# FSPDL_50_5-51Hz.net
KiCad netlist of a schematic drawn in EasyEDA
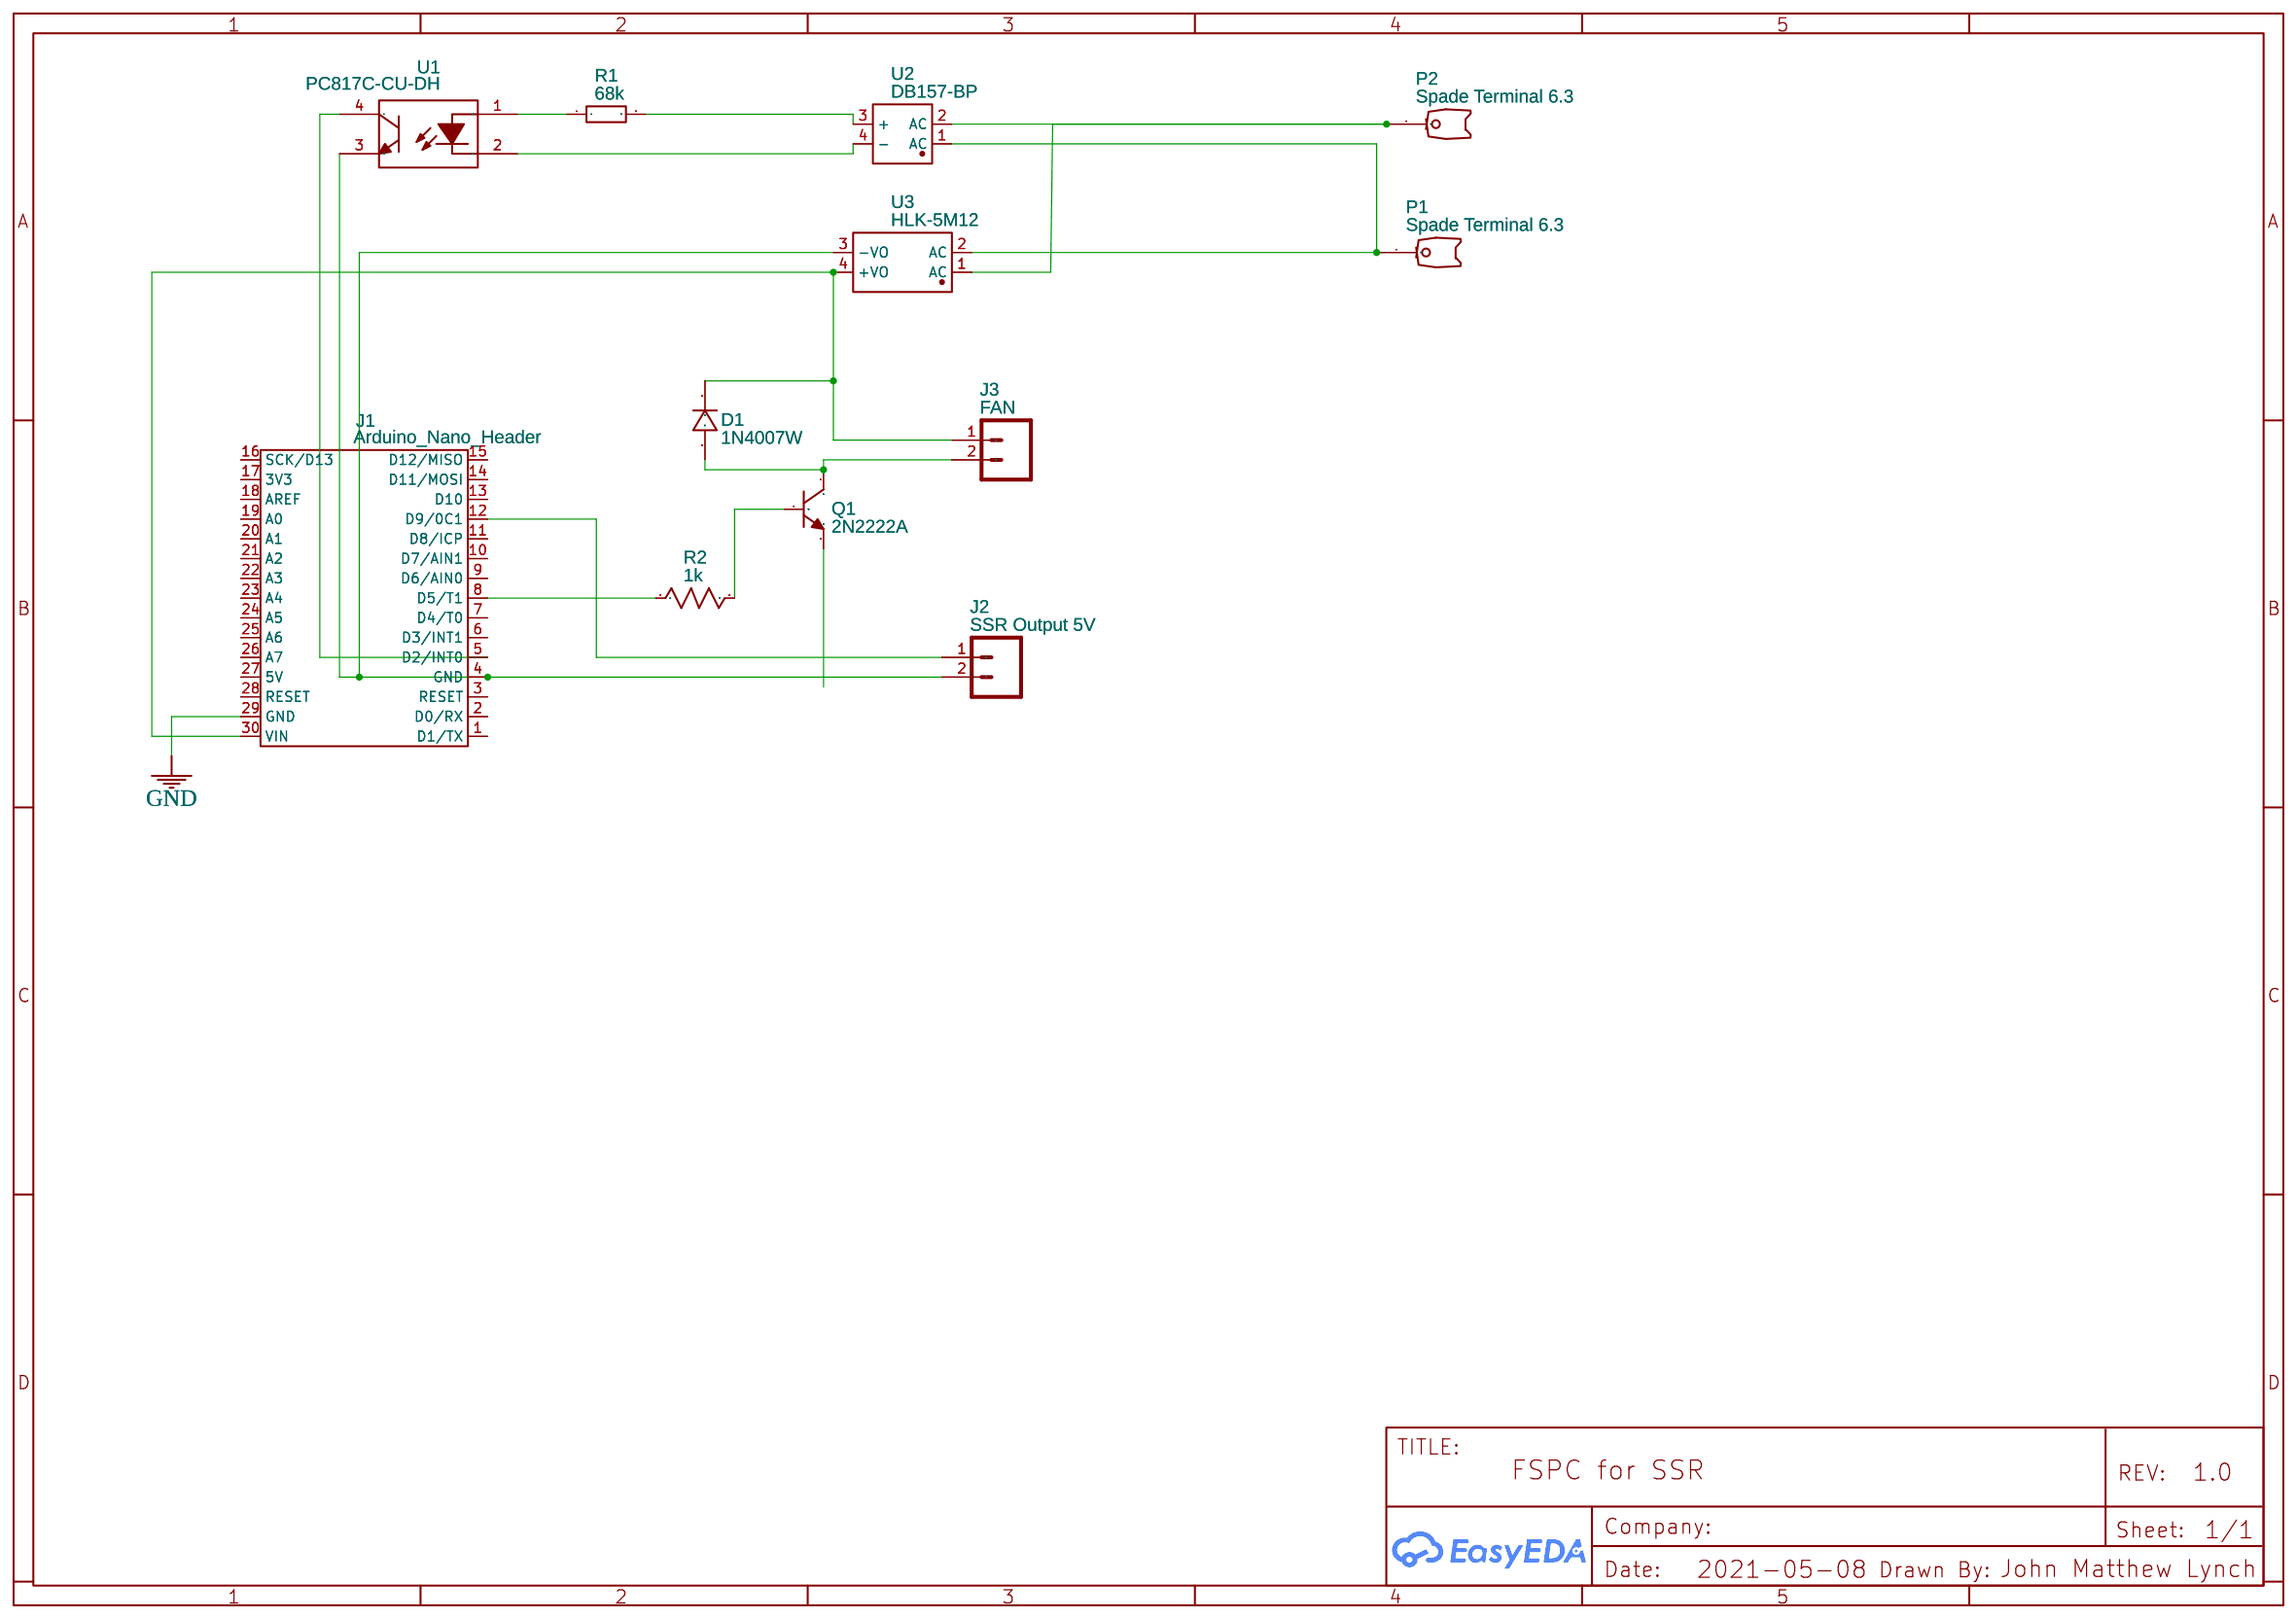
[diagram p0: schematic sheet]

(export (version "E")
  (design (tool "Eeschema 10.0.6"))
  (components
    (comp (ref "D1")
      (value "1N4007W")
      (fields (field (name "BOM_Supplier Part") "C328592"))
      (libsource (lib "") (part "1N4007W"))
    )
    (comp (ref "J1") (value "Arduino_Nano_Header") (libsource (lib "") (part "Arduino_Nano_Header")))
    (comp (ref "J2") (value "SSR Output 5V") (libsource (lib "") (part "CONN_02JST-PTH-2")))
    (comp (ref "J3") (value "FAN") (libsource (lib "") (part "CONN_02JST-PTH-2")))
    (comp (ref "P1")
      (value "Spade Terminal 6.3")
      (fields (field (name "BOM_Manufacturer Part") "1287") (field (name "BOM_Supplier Part") "C238078"))
      (libsource (lib "") (part "Spade Terminal 6.3"))
    )
    (comp (ref "P2")
      (value "Spade Terminal 6.3")
      (fields (field (name "BOM_Manufacturer Part") "1287") (field (name "BOM_Supplier Part") "C238078"))
      (libsource (lib "") (part "Spade Terminal 6.3"))
    )
    (comp (ref "Q1")
      (value "2N2222A")
      (fields (field (name "Manufacturer") "BLUE ROCKET(蓝箭)"))
      (libsource (lib "") (part "2N2222A"))
    )
    (comp (ref "R1")
      (value "68k")
      (fields (field (name "BOM_Supplier Part") "C119513"))
      (libsource (lib "") (part "1W 68K"))
    )
    (comp (ref "R2") (value "1k") (libsource (lib "") (part "R_0603_US")))
    (comp (ref "U1")
      (value "PC817C-CU-DH")
      (fields (field (name "BOM_Supplier Part") "C427589"))
      (libsource (lib "") (part "PC817C-CU-DH"))
    )
    (comp (ref "U2")
      (value "DB157-BP")
      (fields (field (name "BOM_Supplier Part") "C2975492"))
      (libsource (lib "") (part "DB157-BP"))
    )
    (comp (ref "U3")
      (value "HLK-5M12")
      (fields (field (name "BOM_Supplier Part") "C209908"))
      (libsource (lib "") (part "HLK-5M12"))
    )
  )
  (nets
    (net (code "1") (name "GND") (class "Default")
      (node (ref "J1") (pin "29") (pinfunction "GND_29") (pintype "unspecified"))
    )
    (net (code "2") (name "Net-(J1-D2{slash}INT0)") (class "Default")
      (node (ref "J1") (pin "5") (pinfunction "D2/INT0_5") (pintype "unspecified"))
      (node (ref "U1") (pin "4") (pinfunction "4_4") (pintype "unspecified"))
    )
    (net (code "3") (name "Net-(J1-D5{slash}T1)") (class "Default")
      (node (ref "J1") (pin "8") (pinfunction "D5/T1_8") (pintype "unspecified"))
      (node (ref "R2") (pin "1") (pinfunction "1_1") (pintype "unspecified"))
    )
    (net (code "4") (name "Net-(J1-D9{slash}0C1)") (class "Default")
      (node (ref "J1") (pin "12") (pinfunction "D9/0C1_12") (pintype "unspecified"))
      (node (ref "J2") (pin "1") (pinfunction "1_1") (pintype "unspecified"))
    )
    (net (code "5") (name "Net-(J1-VIN)") (class "Default")
      (node (ref "D1") (pin "1") (pinfunction "1_1") (pintype "unspecified"))
      (node (ref "J1") (pin "30") (pinfunction "VIN_30") (pintype "unspecified"))
      (node (ref "J3") (pin "1") (pinfunction "1_1") (pintype "unspecified"))
      (node (ref "U3") (pin "4") (pinfunction "+VO_4") (pintype "unspecified"))
    )
    (net (code "6") (name "Net-(P1-Pad1)") (class "Default")
      (node (ref "P1") (pin "1") (pinfunction "1_1") (pintype "unspecified"))
      (node (ref "U2") (pin "1") (pinfunction "AC_1") (pintype "unspecified"))
      (node (ref "U3") (pin "2") (pinfunction "AC_2") (pintype "unspecified"))
    )
    (net (code "7") (name "Net-(P2-Pad1)") (class "Default")
      (node (ref "P2") (pin "1") (pinfunction "1_1") (pintype "unspecified"))
      (node (ref "U2") (pin "2") (pinfunction "AC_2") (pintype "unspecified"))
      (node (ref "U3") (pin "1") (pinfunction "AC_1") (pintype "unspecified"))
    )
    (net (code "8") (name "Net-(Q1-B)") (class "Default")
      (node (ref "Q1") (pin "2") (pinfunction "B_2") (pintype "unspecified"))
      (node (ref "R2") (pin "2") (pinfunction "2_2") (pintype "unspecified"))
    )
    (net (code "9") (name "Net-(Q1-C)") (class "Default")
      (node (ref "D1") (pin "2") (pinfunction "2_2") (pintype "unspecified"))
      (node (ref "J3") (pin "2") (pinfunction "2_2") (pintype "unspecified"))
      (node (ref "Q1") (pin "1") (pinfunction "C_1") (pintype "unspecified"))
    )
    (net (code "10") (name "Net-(R1-Pad1)") (class "Default")
      (node (ref "R1") (pin "1") (pinfunction "1_1") (pintype "unspecified"))
      (node (ref "U1") (pin "1") (pinfunction "1_1") (pintype "unspecified"))
    )
    (net (code "11") (name "Net-(U2-+)") (class "Default")
      (node (ref "R1") (pin "2") (pinfunction "2_2") (pintype "unspecified"))
      (node (ref "U2") (pin "3") (pinfunction "+_3") (pintype "unspecified"))
    )
    (net (code "12") (name "Net-(U2--)") (class "Default")
      (node (ref "U1") (pin "2") (pinfunction "2_2") (pintype "unspecified"))
      (node (ref "U2") (pin "4") (pinfunction "-_4") (pintype "unspecified"))
    )
    (net (code "13") (name "Net-(U3--VO)") (class "Default")
      (node (ref "J1") (pin "4") (pinfunction "GND_4") (pintype "unspecified"))
      (node (ref "J2") (pin "2") (pinfunction "2_2") (pintype "unspecified"))
      (node (ref "U1") (pin "3") (pinfunction "3_3") (pintype "unspecified"))
      (node (ref "U3") (pin "3") (pinfunction "-VO_3") (pintype "unspecified"))
    )
    (net (code "14") (name "unconnected-(J1-3V3-Pad17)") (class "Default")
      (node (ref "J1") (pin "17") (pinfunction "3V3_17") (pintype "unspecified"))
    )
    (net (code "15") (name "unconnected-(J1-5V-Pad27)") (class "Default")
      (node (ref "J1") (pin "27") (pinfunction "5V_27") (pintype "unspecified"))
    )
    (net (code "16") (name "unconnected-(J1-A0-Pad19)") (class "Default")
      (node (ref "J1") (pin "19") (pinfunction "A0_19") (pintype "unspecified"))
    )
    (net (code "17") (name "unconnected-(J1-A1-Pad20)") (class "Default")
      (node (ref "J1") (pin "20") (pinfunction "A1_20") (pintype "unspecified"))
    )
    (net (code "18") (name "unconnected-(J1-A2-Pad21)") (class "Default")
      (node (ref "J1") (pin "21") (pinfunction "A2_21") (pintype "unspecified"))
    )
    (net (code "19") (name "unconnected-(J1-A3-Pad22)") (class "Default")
      (node (ref "J1") (pin "22") (pinfunction "A3_22") (pintype "unspecified"))
    )
    (net (code "20") (name "unconnected-(J1-A4-Pad23)") (class "Default")
      (node (ref "J1") (pin "23") (pinfunction "A4_23") (pintype "unspecified"))
    )
    (net (code "21") (name "unconnected-(J1-A5-Pad24)") (class "Default")
      (node (ref "J1") (pin "24") (pinfunction "A5_24") (pintype "unspecified"))
    )
    (net (code "22") (name "unconnected-(J1-A6-Pad25)") (class "Default")
      (node (ref "J1") (pin "25") (pinfunction "A6_25") (pintype "unspecified"))
    )
    (net (code "23") (name "unconnected-(J1-A7-Pad26)") (class "Default")
      (node (ref "J1") (pin "26") (pinfunction "A7_26") (pintype "unspecified"))
    )
    (net (code "24") (name "unconnected-(J1-AREF-Pad18)") (class "Default")
      (node (ref "J1") (pin "18") (pinfunction "AREF_18") (pintype "unspecified"))
    )
    (net (code "25") (name "unconnected-(J1-D0{slash}RX-Pad2)") (class "Default")
      (node (ref "J1") (pin "2") (pinfunction "D0/RX_2") (pintype "unspecified"))
    )
    (net (code "26") (name "unconnected-(J1-D1{slash}TX-Pad1)") (class "Default")
      (node (ref "J1") (pin "1") (pinfunction "D1/TX_1") (pintype "unspecified"))
    )
    (net (code "27") (name "unconnected-(J1-D3{slash}INT1-Pad6)") (class "Default")
      (node (ref "J1") (pin "6") (pinfunction "D3/INT1_6") (pintype "unspecified"))
    )
    (net (code "28") (name "unconnected-(J1-D4{slash}T0-Pad7)") (class "Default")
      (node (ref "J1") (pin "7") (pinfunction "D4/T0_7") (pintype "unspecified"))
    )
    (net (code "29") (name "unconnected-(J1-D6{slash}AIN0-Pad9)") (class "Default")
      (node (ref "J1") (pin "9") (pinfunction "D6/AIN0_9") (pintype "unspecified"))
    )
    (net (code "30") (name "unconnected-(J1-D7{slash}AIN1-Pad10)") (class "Default")
      (node (ref "J1") (pin "10") (pinfunction "D7/AIN1_10") (pintype "unspecified"))
    )
    (net (code "31") (name "unconnected-(J1-D8{slash}ICP-Pad11)") (class "Default")
      (node (ref "J1") (pin "11") (pinfunction "D8/ICP_11") (pintype "unspecified"))
    )
    (net (code "32") (name "unconnected-(J1-D10-Pad13)") (class "Default")
      (node (ref "J1") (pin "13") (pinfunction "D10_13") (pintype "unspecified"))
    )
    (net (code "33") (name "unconnected-(J1-D11{slash}MOSI-Pad14)") (class "Default")
      (node (ref "J1") (pin "14") (pinfunction "D11/MOSI_14") (pintype "unspecified"))
    )
    (net (code "34") (name "unconnected-(J1-D12{slash}MISO-Pad15)") (class "Default")
      (node (ref "J1") (pin "15") (pinfunction "D12/MISO_15") (pintype "unspecified"))
    )
    (net (code "35") (name "unconnected-(J1-RESET-Pad3)") (class "Default")
      (node (ref "J1") (pin "3") (pinfunction "RESET_3") (pintype "unspecified"))
    )
    (net (code "36") (name "unconnected-(J1-RESET-Pad28)") (class "Default")
      (node (ref "J1") (pin "28") (pinfunction "RESET_28") (pintype "unspecified"))
    )
    (net (code "37") (name "unconnected-(J1-SCK{slash}D13-Pad16)") (class "Default")
      (node (ref "J1") (pin "16") (pinfunction "SCK/D13_16") (pintype "unspecified"))
    )
    (net (code "38") (name "unconnected-(Q1-E-Pad3)") (class "Default")
      (node (ref "Q1") (pin "3") (pinfunction "E_3") (pintype "unspecified"))
    )
  )
)
